# MAX31855-K-THERMOCOUPLE_METER.net
KiCad netlist of a schematic drawn in EasyEDA Pro
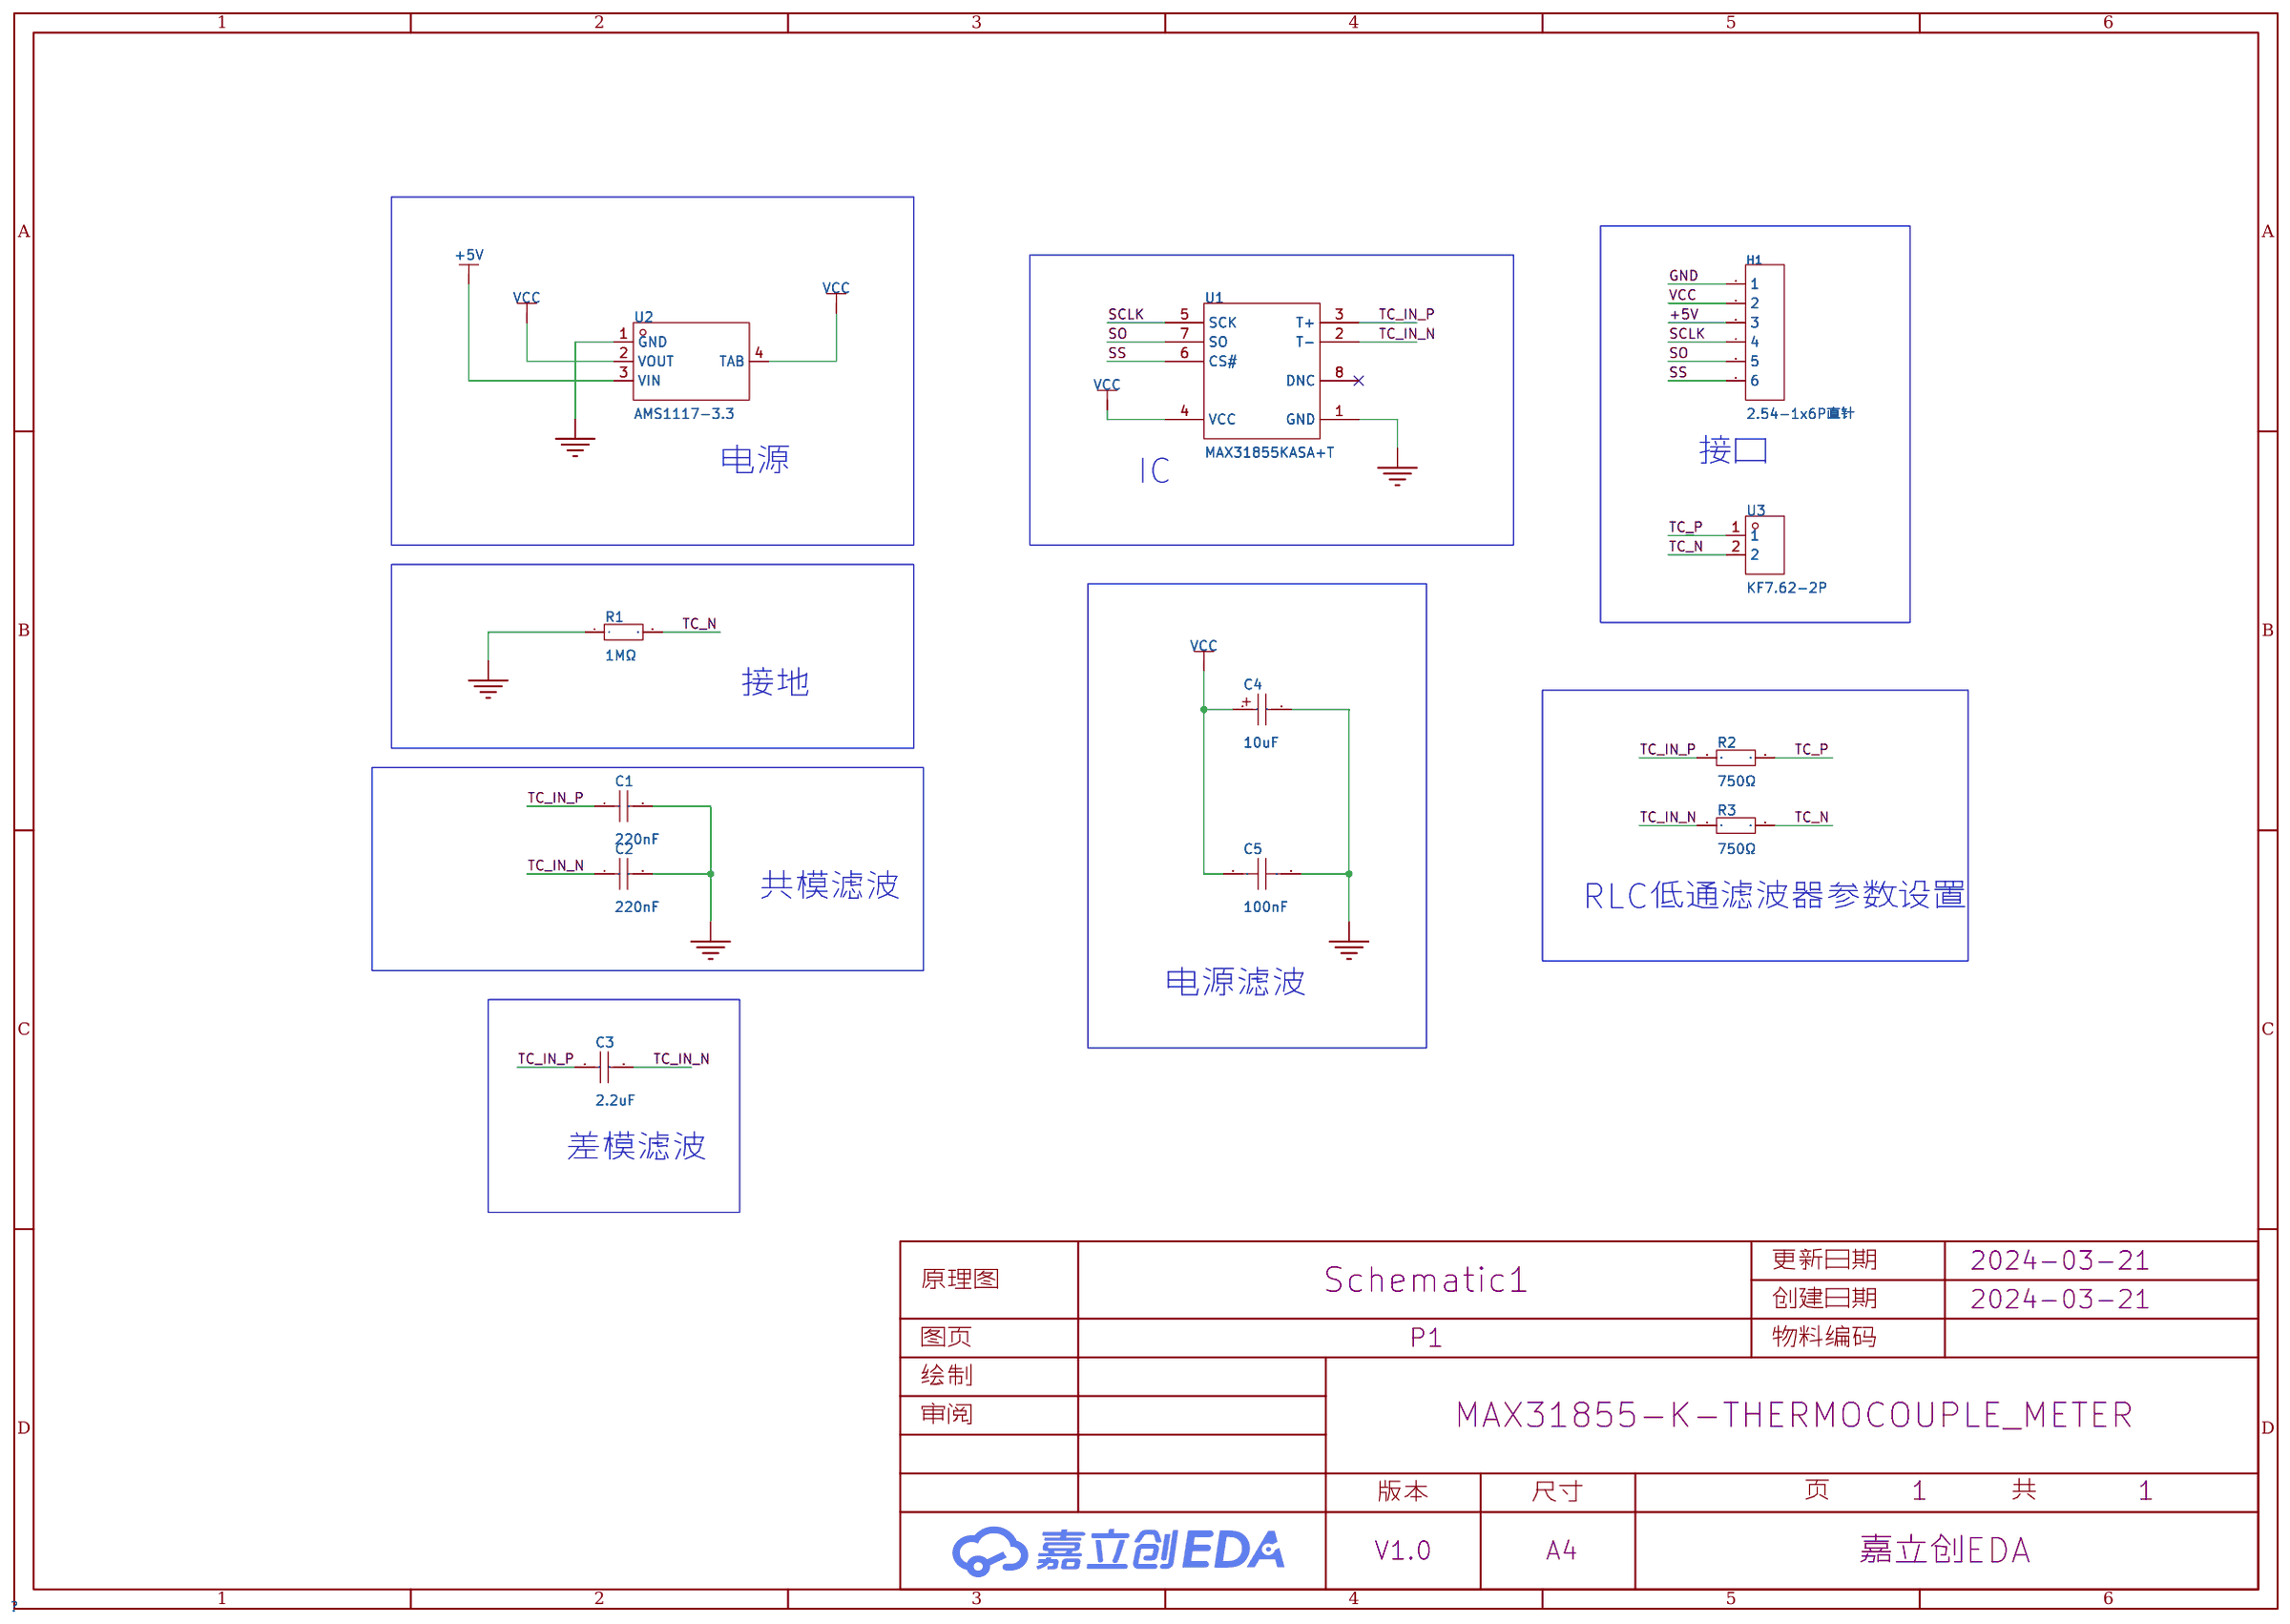
[diagram p0: schematic sheet]

(export (version "E")
  (design (tool "Eeschema 10.0.6"))
  (components
    (comp (ref "C1")
      (value "220nF")
      (footprint "easyedapro:C0603")
      (description "容值:220nF;精度:±10%;额定电压:50V;材质(温度系数):X7R;")
      (fields
        (field (name "Manufacturer Part") "CC0603KRX7R9BB224")
        (field (name "Manufacturer") "YAGEO(国巨)")
      )
      (libsource (lib "easyedapro") (part "CC0603KRX7R9BB224"))
    )
    (comp (ref "C2")
      (value "220nF")
      (footprint "easyedapro:C0603")
      (description "容值:220nF;精度:±10%;额定电压:50V;材质(温度系数):X7R;")
      (fields
        (field (name "Manufacturer Part") "CC0603KRX7R9BB224")
        (field (name "Manufacturer") "YAGEO(国巨)")
      )
      (libsource (lib "easyedapro") (part "CC0603KRX7R9BB224"))
    )
    (comp (ref "C3")
      (value "2.2uF")
      (footprint "easyedapro:C0603")
      (description "容值:2.2uF;精度:±10%;额定电压:16V;材质(温度系数):X5R;")
      (fields
        (field (name "Manufacturer Part") "CL10A225KO8NNNC")
        (field (name "Manufacturer") "SAMSUNG(三星)")
      )
      (libsource (lib "easyedapro") (part "CL10A225KO8NNNC"))
    )
    (comp (ref "C4")
      (value "10uF")
      (footprint "easyedapro:CAP-SMD_L3.2-W1.6-RD")
      (description "容值:10uF;精度:±10%;额定电压:16V;等效串联电阻:10Ω@100kHz;")
      (fields
        (field (name "Manufacturer Part") "CA45-A-16V-10uF-K")
        (field (name "Manufacturer") "CEC(振华新云)")
      )
      (libsource (lib "easyedapro") (part "CA45-A-16V-10UF-K"))
    )
    (comp (ref "C5")
      (value "100nF")
      (footprint "easyedapro:C0603")
      (description "容值:100nF;精度:±10%;额定电压:50V;材质(温度系数):X7R;")
      (fields
        (field (name "Manufacturer Part") "CC0603KRX7R9BB104")
        (field (name "Manufacturer") "YAGEO(国巨)")
      )
      (libsource (lib "easyedapro") (part "CC0603KRX7R9BB104"))
    )
    (comp (ref "H1")
      (value "2.54-1x6P直针")
      (footprint "easyedapro:HDR-TH_6P-P2.54-V-M-1")
      (fields (field (name "Manufacturer") "BOOMELE(博穆精密)"))
      (libsource (lib "easyedapro") (part "Header-Male-2.54_1x6"))
    )
    (comp (ref "R1")
      (value "1MΩ")
      (footprint "easyedapro:R0402")
      (description "电阻类型:厚膜电阻;阻值:1MΩ;精度:±1%;功率:62.5mW;最大工作电压:50V;温度系数:±100ppm/°C;")
      (fields
        (field (name "Manufacturer Part") "0402WGF1004TCE")
        (field (name "Manufacturer") "UNI-ROYAL(厚声)")
      )
      (libsource (lib "easyedapro") (part "0402WGF1004TCE"))
    )
    (comp (ref "R2")
      (value "750Ω")
      (footprint "easyedapro:R0603")
      (description "电阻类型:厚膜电阻;阻值:750Ω;精度:±1%;功率:100mW;最大工作电压:75V;温度系数:±100ppm/°C;")
      (fields
        (field (name "Manufacturer Part") "0603WAF7500T5E")
        (field (name "Manufacturer") "UNI-ROYAL(厚声)")
      )
      (libsource (lib "easyedapro") (part "0603WAF7500T5E"))
    )
    (comp (ref "R3")
      (value "750Ω")
      (footprint "easyedapro:R0603")
      (description "电阻类型:厚膜电阻;阻值:750Ω;精度:±1%;功率:100mW;最大工作电压:75V;温度系数:±100ppm/°C;")
      (fields
        (field (name "Manufacturer Part") "0603WAF7500T5E")
        (field (name "Manufacturer") "UNI-ROYAL(厚声)")
      )
      (libsource (lib "easyedapro") (part "0603WAF7500T5E"))
    )
    (comp (ref "U1")
      (value "MAX31855KASA+T")
      (footprint "easyedapro:SO-8_L4.9-W3.9-P1.27-LS5.9-BL")
      (description "冷端补偿热电偶至数字输出转换器、高精度热电偶数字转换器IC，有效简化设计并降低系统成本")
      (fields (field (name "Manufacturer") "ADI(亚德诺)/MAXIM(美信)"))
      (libsource (lib "easyedapro") (part "MAX31855KASA+T"))
    )
    (comp (ref "U2")
      (value "AMS1117-3.3")
      (footprint "easyedapro:SOT-223-3_L6.5-W3.5-P3.05-LS7.0")
      (description "输出类型：固定 输出极性：正 最大输入电压：18V 输出电压：3.3V 输出电流：1A 电源纹波抑制比(PSRR)：60dB@(120Hz)。当前应用较多领域：三端稳压器，机顶盒")
      (fields (field (name "Manufacturer") "TWGMC(台湾迪嘉)"))
      (libsource (lib "easyedapro") (part "AMS1117-3.3_C5250992"))
    )
    (comp (ref "U3")
      (value "KF7.62-2P")
      (footprint "easyedapro:CONN-TH_KF7.62-2P")
      (fields (field (name "Manufacturer") "KEFA(科发)"))
      (libsource (lib "easyedapro") (part "KF7.62-2P"))
    )
  )
  (nets
    (net (code "1") (name "+5V") (class "Default")
      (node (ref "H1") (pin "3") (pinfunction "3_3") (pintype "input"))
      (node (ref "U2") (pin "3") (pinfunction "VIN_3") (pintype "unspecified"))
    )
    (net (code "2") (name "/SCLK") (class "Default")
      (node (ref "H1") (pin "4") (pinfunction "4_4") (pintype "input"))
      (node (ref "U1") (pin "5") (pinfunction "SCK_5") (pintype "unspecified"))
    )
    (net (code "3") (name "/SO") (class "Default")
      (node (ref "H1") (pin "5") (pinfunction "5_5") (pintype "input"))
      (node (ref "U1") (pin "7") (pinfunction "SO_7") (pintype "output"))
    )
    (net (code "4") (name "/SS") (class "Default")
      (node (ref "H1") (pin "6") (pinfunction "6_6") (pintype "input"))
      (node (ref "U1") (pin "6") (pinfunction "CS#_6") (pintype "unspecified"))
    )
    (net (code "5") (name "/TC_IN_N") (class "Default")
      (node (ref "C2") (pin "1") (pinfunction "1_1") (pintype "input"))
      (node (ref "C3") (pin "2") (pinfunction "2_2") (pintype "input"))
      (node (ref "R3") (pin "1") (pinfunction "1_1") (pintype "input"))
      (node (ref "U1") (pin "2") (pinfunction "T-_2") (pintype "unspecified"))
    )
    (net (code "6") (name "/TC_IN_P") (class "Default")
      (node (ref "C1") (pin "1") (pinfunction "1_1") (pintype "input"))
      (node (ref "C3") (pin "1") (pinfunction "1_1") (pintype "input"))
      (node (ref "R2") (pin "1") (pinfunction "1_1") (pintype "input"))
      (node (ref "U1") (pin "3") (pinfunction "T+_3") (pintype "unspecified"))
    )
    (net (code "7") (name "/TC_N") (class "Default")
      (node (ref "R1") (pin "2") (pinfunction "2_2") (pintype "input"))
      (node (ref "R3") (pin "2") (pinfunction "2_2") (pintype "input"))
      (node (ref "U3") (pin "2") (pinfunction "2_2") (pintype "unspecified"))
    )
    (net (code "8") (name "/TC_P") (class "Default")
      (node (ref "R2") (pin "2") (pinfunction "2_2") (pintype "input"))
      (node (ref "U3") (pin "1") (pinfunction "1_1") (pintype "unspecified"))
    )
    (net (code "9") (name "GND") (class "Default")
      (node (ref "C1") (pin "2") (pinfunction "2_2") (pintype "input"))
      (node (ref "C2") (pin "2") (pinfunction "2_2") (pintype "input"))
      (node (ref "C4") (pin "2") (pinfunction "2_2") (pintype "input"))
      (node (ref "C5") (pin "2") (pinfunction "2_2") (pintype "unspecified"))
      (node (ref "H1") (pin "1") (pinfunction "1_1") (pintype "input"))
      (node (ref "R1") (pin "1") (pinfunction "1_1") (pintype "input"))
      (node (ref "U1") (pin "1") (pinfunction "GND_1") (pintype "unspecified"))
      (node (ref "U2") (pin "1") (pinfunction "GND_1") (pintype "unspecified"))
    )
    (net (code "10") (name "VCC") (class "Default")
      (node (ref "C4") (pin "1") (pinfunction "1_1") (pintype "input"))
      (node (ref "C5") (pin "1") (pinfunction "1_1") (pintype "unspecified"))
      (node (ref "H1") (pin "2") (pinfunction "2_2") (pintype "input"))
      (node (ref "U1") (pin "4") (pinfunction "VCC_4") (pintype "unspecified"))
      (node (ref "U2") (pin "2") (pinfunction "VOUT_2") (pintype "unspecified"))
      (node (ref "U2") (pin "4") (pinfunction "TAB_4") (pintype "unspecified"))
    )
    (net (code "11") (name "unconnected-(U1-DNC-Pad8)") (class "Default")
      (node (ref "U1") (pin "8") (pinfunction "DNC_8") (pintype "unspecified+no_connect"))
    )
  )
)
